# MicrobitBoardExtend.net
KiCad netlist of a schematic drawn in Altium Designer
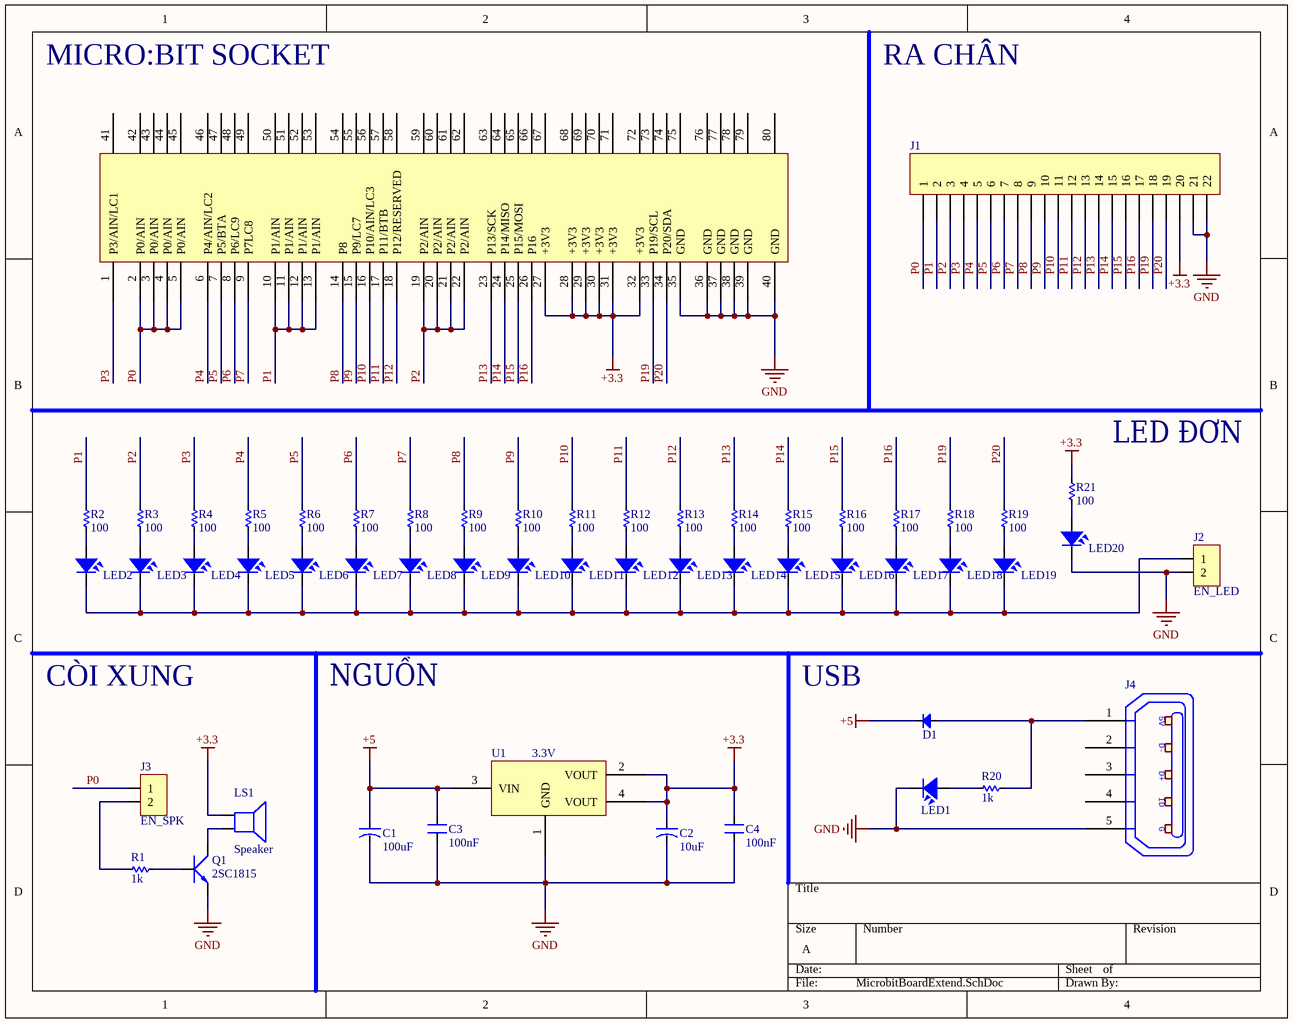
[diagram p0: MicrobitBoardExtend.SchDoc]

(export (version "E")
  (design (tool "Eeschema 10.0.6"))
  (components
    (comp (ref "BBC1")
      (value "BBC_SOCKET")
      (footprint "BBC_SK_DIP")
      (libsource (lib "microbit") (part "BBC_SOCKET"))
    )
    (comp (ref "C1")
      (value "100uF")
      (footprint "CA-ALU-6.3")
      (description "Capacitor (Semiconductor SIM Model)")
      (fields (field (name "PUBLISHER") "Altium Limited"))
      (libsource (lib "LIBRARY") (part "CN-ALU-DIP"))
    )
    (comp (ref "C2")
      (value "10uF")
      (footprint "CA-ALU-5")
      (description "Capacitor (Semiconductor SIM Model)")
      (fields (field (name "PUBLISHER") "Altium Limited"))
      (libsource (lib "LIBRARY") (part "CN-ALU-DIP"))
    )
    (comp (ref "C3") (value "100nF") (footprint "CN-SMD-0805") (libsource (lib "LIBRARY") (part "CN")))
    (comp (ref "C4") (value "100nF") (footprint "CN-SMD-0805") (libsource (lib "LIBRARY") (part "CN")))
    (comp (ref "D1")
      (value "SS34")
      (footprint "DIO-SMD-106")
      (description "Default Diode")
      (fields (field (name "PUBLISHER") "Altium Limited"))
      (libsource (lib "LIBRARY") (part "Diode SMD"))
    )
    (comp (ref "J1")
      (value "JP22")
      (footprint "JP22-D1T")
      (description "WR-PHD 2.54 mm Angled Socket Header")
      (fields
        (field (name "MANUFACTURER") "Würth Elektronik eiSos GmbH")
        (field (name "PARTNO") "613022143121")
        (field (name "CREATED BY") "Karrer Zheng")
      )
      (libsource (lib "LIBRARY") (part "JP22"))
    )
    (comp (ref "J2")
      (value "EN_LED")
      (footprint "JP2-CLOSED")
      (description "WR-PHD 2.54 mm Angled Socket Header")
      (fields
        (field (name "MANUFACTURER") "Würth Elektronik eiSos GmbH")
        (field (name "PARTNO") "613002143121")
        (field (name "CREATED BY") "Karrer Zheng")
      )
      (libsource (lib "LIBRARY") (part "JP2"))
    )
    (comp (ref "J3")
      (value "EN_SPK")
      (footprint "JP2-CLOSED")
      (description "WR-PHD 2.54 mm Angled Socket Header")
      (fields
        (field (name "MANUFACTURER") "Würth Elektronik eiSos GmbH")
        (field (name "PARTNO") "613002143121")
        (field (name "CREATED BY") "Karrer Zheng")
      )
      (libsource (lib "LIBRARY") (part "JP2"))
    )
    (comp (ref "J4")
      (value "PWR")
      (footprint "USB-M1")
      (fields
        (field (name "MANUFACTURER") "FCI")
        (field (name "MANUFACTURER PART NUMBER") "10118193-0001LF")
        (field (name ".CREATOR") "MM")
        (field (name ".CHECKED PCB") "RF")
        (field (name ".CHECKED SCH") "MM")
      )
      (libsource (lib "LIBRARY") (part "USB-5"))
    )
    (comp (ref "LED1")
      (value "PWR")
      (footprint "LED-0805-Green")
      (libsource (lib "LIBRARY") (part "LED SMD"))
    )
    (comp (ref "LED2")
      (value "LED")
      (footprint "LED-3MM-BLUE")
      (description "LED Single colour Green and Red")
      (libsource (lib "LIBRARY") (part "LED"))
    )
    (comp (ref "LED3")
      (value "LED")
      (footprint "LED-3MM-BLUE")
      (description "LED Single colour Green and Red")
      (libsource (lib "LIBRARY") (part "LED"))
    )
    (comp (ref "LED4")
      (value "LED")
      (footprint "LED-3MM-BLUE")
      (description "LED Single colour Green and Red")
      (libsource (lib "LIBRARY") (part "LED"))
    )
    (comp (ref "LED5")
      (value "LED")
      (footprint "LED-3MM-BLUE")
      (description "LED Single colour Green and Red")
      (libsource (lib "LIBRARY") (part "LED"))
    )
    (comp (ref "LED6")
      (value "LED")
      (footprint "LED-3MM-BLUE")
      (description "LED Single colour Green and Red")
      (libsource (lib "LIBRARY") (part "LED"))
    )
    (comp (ref "LED7")
      (value "LED")
      (footprint "LED-3MM-BLUE")
      (description "LED Single colour Green and Red")
      (libsource (lib "LIBRARY") (part "LED"))
    )
    (comp (ref "LED8")
      (value "LED")
      (footprint "LED-3MM-BLUE")
      (description "LED Single colour Green and Red")
      (libsource (lib "LIBRARY") (part "LED"))
    )
    (comp (ref "LED9")
      (value "LED")
      (footprint "LED-3MM-BLUE")
      (description "LED Single colour Green and Red")
      (libsource (lib "LIBRARY") (part "LED"))
    )
    (comp (ref "LED10")
      (value "LED")
      (footprint "LED-3MM-BLUE")
      (description "LED Single colour Green and Red")
      (libsource (lib "LIBRARY") (part "LED"))
    )
    (comp (ref "LED11")
      (value "LED")
      (footprint "LED-3MM-BLUE")
      (description "LED Single colour Green and Red")
      (libsource (lib "LIBRARY") (part "LED"))
    )
    (comp (ref "LED12")
      (value "LED")
      (footprint "LED-3MM-BLUE")
      (description "LED Single colour Green and Red")
      (libsource (lib "LIBRARY") (part "LED"))
    )
    (comp (ref "LED13")
      (value "LED")
      (footprint "LED-3MM-BLUE")
      (description "LED Single colour Green and Red")
      (libsource (lib "LIBRARY") (part "LED"))
    )
    (comp (ref "LED14")
      (value "LED")
      (footprint "LED-3MM-BLUE")
      (description "LED Single colour Green and Red")
      (libsource (lib "LIBRARY") (part "LED"))
    )
    (comp (ref "LED15")
      (value "LED")
      (footprint "LED-3MM-BLUE")
      (description "LED Single colour Green and Red")
      (libsource (lib "LIBRARY") (part "LED"))
    )
    (comp (ref "LED16")
      (value "LED")
      (footprint "LED-3MM-BLUE")
      (description "LED Single colour Green and Red")
      (libsource (lib "LIBRARY") (part "LED"))
    )
    (comp (ref "LED17")
      (value "LED")
      (footprint "LED-3MM-BLUE")
      (description "LED Single colour Green and Red")
      (libsource (lib "LIBRARY") (part "LED"))
    )
    (comp (ref "LED18")
      (value "LED")
      (footprint "LED-3MM-BLUE")
      (description "LED Single colour Green and Red")
      (libsource (lib "LIBRARY") (part "LED"))
    )
    (comp (ref "LED19")
      (value "LED")
      (footprint "LED-3MM-BLUE")
      (description "LED Single colour Green and Red")
      (libsource (lib "LIBRARY") (part "LED"))
    )
    (comp (ref "LED20")
      (value "3V3")
      (footprint "LED-0805-Green")
      (libsource (lib "LIBRARY") (part "LED SMD"))
    )
    (comp (ref "LS1")
      (value "Speaker")
      (footprint "SPEAKER")
      (description "Loudspeaker")
      (fields (field (name "PUBLISHER") "Altium Limited"))
      (libsource (lib "LIBRARY") (part "Speaker"))
    )
    (comp (ref "Q1")
      (value "2SC1815")
      (footprint "SOT23-321")
      (description "NPN 600mW, ECB")
      (libsource (lib "LIBRARY") (part "2SC1815"))
    )
    (comp (ref "R1")
      (value "1k")
      (footprint "RES-SMD-0805")
      (description "Resistor")
      (fields
        (field (name "MANUFACTURER") "Generic Components")
        (field (name "PUBLISHER") "Altium Hobart Technology Centre")
      )
      (libsource (lib "LIBRARY") (part "Res-SMD"))
    )
    (comp (ref "R2")
      (value "100")
      (footprint "RES-SMD-0805")
      (description "Resistor")
      (fields
        (field (name "MANUFACTURER") "Generic Components")
        (field (name "PUBLISHER") "Altium Hobart Technology Centre")
      )
      (libsource (lib "LIBRARY") (part "Res-SMD"))
    )
    (comp (ref "R3")
      (value "100")
      (footprint "RES-SMD-0805")
      (description "Resistor")
      (fields
        (field (name "MANUFACTURER") "Generic Components")
        (field (name "PUBLISHER") "Altium Hobart Technology Centre")
      )
      (libsource (lib "LIBRARY") (part "Res-SMD"))
    )
    (comp (ref "R4")
      (value "100")
      (footprint "RES-SMD-0805")
      (description "Resistor")
      (fields
        (field (name "MANUFACTURER") "Generic Components")
        (field (name "PUBLISHER") "Altium Hobart Technology Centre")
      )
      (libsource (lib "LIBRARY") (part "Res-SMD"))
    )
    (comp (ref "R5")
      (value "100")
      (footprint "RES-SMD-0805")
      (description "Resistor")
      (fields
        (field (name "MANUFACTURER") "Generic Components")
        (field (name "PUBLISHER") "Altium Hobart Technology Centre")
      )
      (libsource (lib "LIBRARY") (part "Res-SMD"))
    )
    (comp (ref "R6")
      (value "100")
      (footprint "RES-SMD-0805")
      (description "Resistor")
      (fields
        (field (name "MANUFACTURER") "Generic Components")
        (field (name "PUBLISHER") "Altium Hobart Technology Centre")
      )
      (libsource (lib "LIBRARY") (part "Res-SMD"))
    )
    (comp (ref "R7")
      (value "100")
      (footprint "RES-SMD-0805")
      (description "Resistor")
      (fields
        (field (name "MANUFACTURER") "Generic Components")
        (field (name "PUBLISHER") "Altium Hobart Technology Centre")
      )
      (libsource (lib "LIBRARY") (part "Res-SMD"))
    )
    (comp (ref "R8")
      (value "100")
      (footprint "RES-SMD-0805")
      (description "Resistor")
      (fields
        (field (name "MANUFACTURER") "Generic Components")
        (field (name "PUBLISHER") "Altium Hobart Technology Centre")
      )
      (libsource (lib "LIBRARY") (part "Res-SMD"))
    )
    (comp (ref "R9")
      (value "100")
      (footprint "RES-SMD-0805")
      (description "Resistor")
      (fields
        (field (name "MANUFACTURER") "Generic Components")
        (field (name "PUBLISHER") "Altium Hobart Technology Centre")
      )
      (libsource (lib "LIBRARY") (part "Res-SMD"))
    )
    (comp (ref "R10")
      (value "100")
      (footprint "RES-SMD-0805")
      (description "Resistor")
      (fields
        (field (name "MANUFACTURER") "Generic Components")
        (field (name "PUBLISHER") "Altium Hobart Technology Centre")
      )
      (libsource (lib "LIBRARY") (part "Res-SMD"))
    )
    (comp (ref "R11")
      (value "100")
      (footprint "RES-SMD-0805")
      (description "Resistor")
      (fields
        (field (name "MANUFACTURER") "Generic Components")
        (field (name "PUBLISHER") "Altium Hobart Technology Centre")
      )
      (libsource (lib "LIBRARY") (part "Res-SMD"))
    )
    (comp (ref "R12")
      (value "100")
      (footprint "RES-SMD-0805")
      (description "Resistor")
      (fields
        (field (name "MANUFACTURER") "Generic Components")
        (field (name "PUBLISHER") "Altium Hobart Technology Centre")
      )
      (libsource (lib "LIBRARY") (part "Res-SMD"))
    )
    (comp (ref "R13")
      (value "100")
      (footprint "RES-SMD-0805")
      (description "Resistor")
      (fields
        (field (name "MANUFACTURER") "Generic Components")
        (field (name "PUBLISHER") "Altium Hobart Technology Centre")
      )
      (libsource (lib "LIBRARY") (part "Res-SMD"))
    )
    (comp (ref "R14")
      (value "100")
      (footprint "RES-SMD-0805")
      (description "Resistor")
      (fields
        (field (name "MANUFACTURER") "Generic Components")
        (field (name "PUBLISHER") "Altium Hobart Technology Centre")
      )
      (libsource (lib "LIBRARY") (part "Res-SMD"))
    )
    (comp (ref "R15")
      (value "100")
      (footprint "RES-SMD-0805")
      (description "Resistor")
      (fields
        (field (name "MANUFACTURER") "Generic Components")
        (field (name "PUBLISHER") "Altium Hobart Technology Centre")
      )
      (libsource (lib "LIBRARY") (part "Res-SMD"))
    )
    (comp (ref "R16")
      (value "100")
      (footprint "RES-SMD-0805")
      (description "Resistor")
      (fields
        (field (name "MANUFACTURER") "Generic Components")
        (field (name "PUBLISHER") "Altium Hobart Technology Centre")
      )
      (libsource (lib "LIBRARY") (part "Res-SMD"))
    )
    (comp (ref "R17")
      (value "100")
      (footprint "RES-SMD-0805")
      (description "Resistor")
      (fields
        (field (name "MANUFACTURER") "Generic Components")
        (field (name "PUBLISHER") "Altium Hobart Technology Centre")
      )
      (libsource (lib "LIBRARY") (part "Res-SMD"))
    )
    (comp (ref "R18")
      (value "100")
      (footprint "RES-SMD-0805")
      (description "Resistor")
      (fields
        (field (name "MANUFACTURER") "Generic Components")
        (field (name "PUBLISHER") "Altium Hobart Technology Centre")
      )
      (libsource (lib "LIBRARY") (part "Res-SMD"))
    )
    (comp (ref "R19")
      (value "100")
      (footprint "RES-SMD-0805")
      (description "Resistor")
      (fields
        (field (name "MANUFACTURER") "Generic Components")
        (field (name "PUBLISHER") "Altium Hobart Technology Centre")
      )
      (libsource (lib "LIBRARY") (part "Res-SMD"))
    )
    (comp (ref "R20")
      (value "1k")
      (footprint "RES-SMD-0805")
      (description "Resistor")
      (fields
        (field (name "MANUFACTURER") "Generic Components")
        (field (name "PUBLISHER") "Altium Hobart Technology Centre")
      )
      (libsource (lib "LIBRARY") (part "Res-SMD"))
    )
    (comp (ref "R21")
      (value "100")
      (footprint "RES-SMD-0805")
      (description "Resistor")
      (fields
        (field (name "MANUFACTURER") "Generic Components")
        (field (name "PUBLISHER") "Altium Hobart Technology Centre")
      )
      (libsource (lib "LIBRARY") (part "Res-SMD"))
    )
    (comp (ref "U1")
      (value "3.3V")
      (footprint "SOT89-150P410X160-3N")
      (description "Dán")
      (libsource (lib "THU VIEN SCH_04042017_1") (part "CJA _ 3.3V"))
    )
  )
  (nets
    (net (code "1") (name "+3.3") (class "Default")
      (node (ref "BBC1") (pin "27") (pinfunction "+3V3_27") (pintype "passive"))
      (node (ref "BBC1") (pin "28") (pinfunction "+3V3_28") (pintype "passive"))
      (node (ref "BBC1") (pin "29") (pinfunction "+3V3_29") (pintype "passive"))
      (node (ref "BBC1") (pin "30") (pinfunction "+3V3_30") (pintype "passive"))
      (node (ref "BBC1") (pin "31") (pinfunction "+3V3_31") (pintype "passive"))
      (node (ref "BBC1") (pin "32") (pinfunction "+3V3_32") (pintype "passive"))
      (node (ref "C2") (pin "1") (pinfunction "1_1") (pintype "passive"))
      (node (ref "C4") (pin "1") (pinfunction "1_1") (pintype "passive"))
      (node (ref "J1") (pin "20") (pinfunction "20_20") (pintype "passive"))
      (node (ref "LS1") (pin "1") (pinfunction "1_1") (pintype "passive"))
      (node (ref "R21") (pin "2") (pinfunction "2_2") (pintype "passive"))
      (node (ref "U1") (pin "2") (pinfunction "VOUT_2") (pintype "passive"))
      (node (ref "U1") (pin "4") (pinfunction "VOUT_4") (pintype "passive"))
    )
    (net (code "2") (name "+5") (class "Default")
      (node (ref "C1") (pin "1") (pinfunction "1_1") (pintype "passive"))
      (node (ref "C3") (pin "1") (pinfunction "1_1") (pintype "passive"))
      (node (ref "D1") (pin "2") (pinfunction "K_2") (pintype "passive"))
      (node (ref "U1") (pin "3") (pinfunction "VIN_3") (pintype "passive"))
    )
    (net (code "3") (name "/P0") (class "Default")
      (node (ref "BBC1") (pin "2") (pinfunction "P0/AIN_2") (pintype "passive"))
      (node (ref "BBC1") (pin "3") (pinfunction "P0/AIN_3") (pintype "passive"))
      (node (ref "BBC1") (pin "4") (pinfunction "P0/AIN_4") (pintype "passive"))
      (node (ref "BBC1") (pin "5") (pinfunction "P0/AIN_5") (pintype "passive"))
      (node (ref "J1") (pin "1") (pinfunction "1_1") (pintype "passive"))
      (node (ref "J3") (pin "1") (pinfunction "1_1") (pintype "passive"))
    )
    (net (code "4") (name "/P1") (class "Default")
      (node (ref "BBC1") (pin "10") (pinfunction "P1/AIN_10") (pintype "passive"))
      (node (ref "BBC1") (pin "11") (pinfunction "P1/AIN_11") (pintype "passive"))
      (node (ref "BBC1") (pin "12") (pinfunction "P1/AIN_12") (pintype "passive"))
      (node (ref "BBC1") (pin "13") (pinfunction "P1/AIN_13") (pintype "passive"))
      (node (ref "J1") (pin "2") (pinfunction "2_2") (pintype "passive"))
      (node (ref "R2") (pin "2") (pinfunction "2_2") (pintype "passive"))
    )
    (net (code "5") (name "/P2") (class "Default")
      (node (ref "BBC1") (pin "19") (pinfunction "P2/AIN_19") (pintype "passive"))
      (node (ref "BBC1") (pin "20") (pinfunction "P2/AIN_20") (pintype "passive"))
      (node (ref "BBC1") (pin "21") (pinfunction "P2/AIN_21") (pintype "passive"))
      (node (ref "BBC1") (pin "22") (pinfunction "P2/AIN_22") (pintype "passive"))
      (node (ref "J1") (pin "3") (pinfunction "3_3") (pintype "passive"))
      (node (ref "R3") (pin "2") (pinfunction "2_2") (pintype "passive"))
    )
    (net (code "6") (name "/P3") (class "Default")
      (node (ref "BBC1") (pin "1") (pinfunction "P3/AIN/LC1_1") (pintype "passive"))
      (node (ref "J1") (pin "4") (pinfunction "4_4") (pintype "passive"))
      (node (ref "R4") (pin "2") (pinfunction "2_2") (pintype "passive"))
    )
    (net (code "7") (name "/P4") (class "Default")
      (node (ref "BBC1") (pin "6") (pinfunction "P4/AIN/LC2_6") (pintype "passive"))
      (node (ref "J1") (pin "5") (pinfunction "5_5") (pintype "passive"))
      (node (ref "R5") (pin "2") (pinfunction "2_2") (pintype "passive"))
    )
    (net (code "8") (name "/P5") (class "Default")
      (node (ref "BBC1") (pin "7") (pinfunction "P5/BTA_7") (pintype "passive"))
      (node (ref "J1") (pin "6") (pinfunction "6_6") (pintype "passive"))
      (node (ref "R6") (pin "2") (pinfunction "2_2") (pintype "passive"))
    )
    (net (code "9") (name "/P6") (class "Default")
      (node (ref "BBC1") (pin "8") (pinfunction "P6/LC9_8") (pintype "passive"))
      (node (ref "J1") (pin "7") (pinfunction "7_7") (pintype "passive"))
      (node (ref "R7") (pin "2") (pinfunction "2_2") (pintype "passive"))
    )
    (net (code "10") (name "/P7") (class "Default")
      (node (ref "BBC1") (pin "9") (pinfunction "P7LC8_9") (pintype "passive"))
      (node (ref "J1") (pin "8") (pinfunction "8_8") (pintype "passive"))
      (node (ref "R8") (pin "2") (pinfunction "2_2") (pintype "passive"))
    )
    (net (code "11") (name "/P8") (class "Default")
      (node (ref "BBC1") (pin "14") (pinfunction "P8_14") (pintype "passive"))
      (node (ref "J1") (pin "9") (pinfunction "9_9") (pintype "passive"))
      (node (ref "R9") (pin "2") (pinfunction "2_2") (pintype "passive"))
    )
    (net (code "12") (name "/P9") (class "Default")
      (node (ref "BBC1") (pin "15") (pinfunction "P9/LC7_15") (pintype "passive"))
      (node (ref "J1") (pin "10") (pinfunction "10_10") (pintype "passive"))
      (node (ref "R10") (pin "2") (pinfunction "2_2") (pintype "passive"))
    )
    (net (code "13") (name "/P10") (class "Default")
      (node (ref "BBC1") (pin "16") (pinfunction "P10/AIN/LC3_16") (pintype "passive"))
      (node (ref "J1") (pin "11") (pinfunction "11_11") (pintype "passive"))
      (node (ref "R11") (pin "2") (pinfunction "2_2") (pintype "passive"))
    )
    (net (code "14") (name "/P11") (class "Default")
      (node (ref "BBC1") (pin "17") (pinfunction "P11/BTB_17") (pintype "passive"))
      (node (ref "J1") (pin "12") (pinfunction "12_12") (pintype "passive"))
      (node (ref "R12") (pin "2") (pinfunction "2_2") (pintype "passive"))
    )
    (net (code "15") (name "/P12") (class "Default")
      (node (ref "BBC1") (pin "18") (pinfunction "P12/RESERVED_18") (pintype "passive"))
      (node (ref "J1") (pin "13") (pinfunction "13_13") (pintype "passive"))
      (node (ref "R13") (pin "2") (pinfunction "2_2") (pintype "passive"))
    )
    (net (code "16") (name "/P13") (class "Default")
      (node (ref "BBC1") (pin "23") (pinfunction "P13/SCK_23") (pintype "passive"))
      (node (ref "J1") (pin "14") (pinfunction "14_14") (pintype "passive"))
      (node (ref "R14") (pin "2") (pinfunction "2_2") (pintype "passive"))
    )
    (net (code "17") (name "/P14") (class "Default")
      (node (ref "BBC1") (pin "24") (pinfunction "P14/MISO_24") (pintype "passive"))
      (node (ref "J1") (pin "15") (pinfunction "15_15") (pintype "passive"))
      (node (ref "R15") (pin "2") (pinfunction "2_2") (pintype "passive"))
    )
    (net (code "18") (name "/P15") (class "Default")
      (node (ref "BBC1") (pin "25") (pinfunction "P15/MOSI_25") (pintype "passive"))
      (node (ref "J1") (pin "16") (pinfunction "16_16") (pintype "passive"))
      (node (ref "R16") (pin "2") (pinfunction "2_2") (pintype "passive"))
    )
    (net (code "19") (name "/P16") (class "Default")
      (node (ref "BBC1") (pin "26") (pinfunction "P16_26") (pintype "passive"))
      (node (ref "J1") (pin "17") (pinfunction "17_17") (pintype "passive"))
      (node (ref "R17") (pin "2") (pinfunction "2_2") (pintype "passive"))
    )
    (net (code "20") (name "/P19") (class "Default")
      (node (ref "BBC1") (pin "33") (pinfunction "P19/SCL_33") (pintype "passive"))
      (node (ref "J1") (pin "18") (pinfunction "18_18") (pintype "passive"))
      (node (ref "R18") (pin "2") (pinfunction "2_2") (pintype "passive"))
    )
    (net (code "21") (name "/P20") (class "Default")
      (node (ref "BBC1") (pin "34") (pinfunction "P20/SDA_34") (pintype "passive"))
      (node (ref "J1") (pin "19") (pinfunction "19_19") (pintype "passive"))
      (node (ref "R19") (pin "2") (pinfunction "2_2") (pintype "passive"))
    )
    (net (code "22") (name "GND") (class "Default")
      (node (ref "BBC1") (pin "35") (pinfunction "GND_35") (pintype "passive"))
      (node (ref "BBC1") (pin "36") (pinfunction "GND_36") (pintype "passive"))
      (node (ref "BBC1") (pin "37") (pinfunction "GND_37") (pintype "passive"))
      (node (ref "BBC1") (pin "38") (pinfunction "GND_38") (pintype "passive"))
      (node (ref "BBC1") (pin "39") (pinfunction "GND_39") (pintype "passive"))
      (node (ref "BBC1") (pin "40") (pinfunction "GND_40") (pintype "passive"))
      (node (ref "C1") (pin "2") (pinfunction "2_2") (pintype "passive"))
      (node (ref "C2") (pin "2") (pinfunction "2_2") (pintype "passive"))
      (node (ref "C3") (pin "2") (pinfunction "2_2") (pintype "passive"))
      (node (ref "C4") (pin "2") (pinfunction "2_2") (pintype "passive"))
      (node (ref "J1") (pin "21") (pinfunction "21_21") (pintype "passive"))
      (node (ref "J1") (pin "22") (pinfunction "22_22") (pintype "passive"))
      (node (ref "J2") (pin "2") (pinfunction "2_2") (pintype "passive"))
      (node (ref "J4") (pin "5") (pinfunction "P5_5") (pintype "passive"))
      (node (ref "LED1") (pin "2") (pinfunction "2_2") (pintype "passive"))
      (node (ref "LED20") (pin "2") (pinfunction "2_2") (pintype "passive"))
      (node (ref "Q1") (pin "1") (pinfunction "E_1") (pintype "passive"))
      (node (ref "U1") (pin "1") (pinfunction "GND_1") (pintype "passive"))
    )
    (net (code "23") (name "Net-(D1-A)") (class "Default")
      (node (ref "D1") (pin "1") (pinfunction "A_1") (pintype "passive"))
      (node (ref "J4") (pin "1") (pinfunction "P1_1") (pintype "passive"))
      (node (ref "R20") (pin "1") (pinfunction "1_1") (pintype "passive"))
    )
    (net (code "24") (name "Net-(J2-Pad1)") (class "Default")
      (node (ref "J2") (pin "1") (pinfunction "1_1") (pintype "passive"))
      (node (ref "LED10") (pin "2") (pinfunction "2_2") (pintype "passive"))
      (node (ref "LED11") (pin "2") (pinfunction "2_2") (pintype "passive"))
      (node (ref "LED12") (pin "2") (pinfunction "2_2") (pintype "passive"))
      (node (ref "LED13") (pin "2") (pinfunction "2_2") (pintype "passive"))
      (node (ref "LED14") (pin "2") (pinfunction "2_2") (pintype "passive"))
      (node (ref "LED15") (pin "2") (pinfunction "2_2") (pintype "passive"))
      (node (ref "LED16") (pin "2") (pinfunction "2_2") (pintype "passive"))
      (node (ref "LED17") (pin "2") (pinfunction "2_2") (pintype "passive"))
      (node (ref "LED18") (pin "2") (pinfunction "2_2") (pintype "passive"))
      (node (ref "LED19") (pin "2") (pinfunction "2_2") (pintype "passive"))
      (node (ref "LED2") (pin "2") (pinfunction "2_2") (pintype "passive"))
      (node (ref "LED3") (pin "2") (pinfunction "2_2") (pintype "passive"))
      (node (ref "LED4") (pin "2") (pinfunction "2_2") (pintype "passive"))
      (node (ref "LED5") (pin "2") (pinfunction "2_2") (pintype "passive"))
      (node (ref "LED6") (pin "2") (pinfunction "2_2") (pintype "passive"))
      (node (ref "LED7") (pin "2") (pinfunction "2_2") (pintype "passive"))
      (node (ref "LED8") (pin "2") (pinfunction "2_2") (pintype "passive"))
      (node (ref "LED9") (pin "2") (pinfunction "2_2") (pintype "passive"))
    )
    (net (code "25") (name "Net-(J3-Pad2)") (class "Default")
      (node (ref "J3") (pin "2") (pinfunction "2_2") (pintype "passive"))
      (node (ref "R1") (pin "2") (pinfunction "2_2") (pintype "passive"))
    )
    (net (code "26") (name "Net-(LED1-Pad1)") (class "Default")
      (node (ref "LED1") (pin "1") (pinfunction "1_1") (pintype "passive"))
      (node (ref "R20") (pin "2") (pinfunction "2_2") (pintype "passive"))
    )
    (net (code "27") (name "Net-(LED2-Pad1)") (class "Default")
      (node (ref "LED2") (pin "1") (pinfunction "1_1") (pintype "passive"))
      (node (ref "R2") (pin "1") (pinfunction "1_1") (pintype "passive"))
    )
    (net (code "28") (name "Net-(LED3-Pad1)") (class "Default")
      (node (ref "LED3") (pin "1") (pinfunction "1_1") (pintype "passive"))
      (node (ref "R3") (pin "1") (pinfunction "1_1") (pintype "passive"))
    )
    (net (code "29") (name "Net-(LED4-Pad1)") (class "Default")
      (node (ref "LED4") (pin "1") (pinfunction "1_1") (pintype "passive"))
      (node (ref "R4") (pin "1") (pinfunction "1_1") (pintype "passive"))
    )
    (net (code "30") (name "Net-(LED5-Pad1)") (class "Default")
      (node (ref "LED5") (pin "1") (pinfunction "1_1") (pintype "passive"))
      (node (ref "R5") (pin "1") (pinfunction "1_1") (pintype "passive"))
    )
    (net (code "31") (name "Net-(LED6-Pad1)") (class "Default")
      (node (ref "LED6") (pin "1") (pinfunction "1_1") (pintype "passive"))
      (node (ref "R6") (pin "1") (pinfunction "1_1") (pintype "passive"))
    )
    (net (code "32") (name "Net-(LED7-Pad1)") (class "Default")
      (node (ref "LED7") (pin "1") (pinfunction "1_1") (pintype "passive"))
      (node (ref "R7") (pin "1") (pinfunction "1_1") (pintype "passive"))
    )
    (net (code "33") (name "Net-(LED8-Pad1)") (class "Default")
      (node (ref "LED8") (pin "1") (pinfunction "1_1") (pintype "passive"))
      (node (ref "R8") (pin "1") (pinfunction "1_1") (pintype "passive"))
    )
    (net (code "34") (name "Net-(LED9-Pad1)") (class "Default")
      (node (ref "LED9") (pin "1") (pinfunction "1_1") (pintype "passive"))
      (node (ref "R9") (pin "1") (pinfunction "1_1") (pintype "passive"))
    )
    (net (code "35") (name "Net-(LED10-Pad1)") (class "Default")
      (node (ref "LED10") (pin "1") (pinfunction "1_1") (pintype "passive"))
      (node (ref "R10") (pin "1") (pinfunction "1_1") (pintype "passive"))
    )
    (net (code "36") (name "Net-(LED11-Pad1)") (class "Default")
      (node (ref "LED11") (pin "1") (pinfunction "1_1") (pintype "passive"))
      (node (ref "R11") (pin "1") (pinfunction "1_1") (pintype "passive"))
    )
    (net (code "37") (name "Net-(LED12-Pad1)") (class "Default")
      (node (ref "LED12") (pin "1") (pinfunction "1_1") (pintype "passive"))
      (node (ref "R12") (pin "1") (pinfunction "1_1") (pintype "passive"))
    )
    (net (code "38") (name "Net-(LED13-Pad1)") (class "Default")
      (node (ref "LED13") (pin "1") (pinfunction "1_1") (pintype "passive"))
      (node (ref "R13") (pin "1") (pinfunction "1_1") (pintype "passive"))
    )
    (net (code "39") (name "Net-(LED14-Pad1)") (class "Default")
      (node (ref "LED14") (pin "1") (pinfunction "1_1") (pintype "passive"))
      (node (ref "R14") (pin "1") (pinfunction "1_1") (pintype "passive"))
    )
    (net (code "40") (name "Net-(LED15-Pad1)") (class "Default")
      (node (ref "LED15") (pin "1") (pinfunction "1_1") (pintype "passive"))
      (node (ref "R15") (pin "1") (pinfunction "1_1") (pintype "passive"))
    )
    (net (code "41") (name "Net-(LED16-Pad1)") (class "Default")
      (node (ref "LED16") (pin "1") (pinfunction "1_1") (pintype "passive"))
      (node (ref "R16") (pin "1") (pinfunction "1_1") (pintype "passive"))
    )
    (net (code "42") (name "Net-(LED17-Pad1)") (class "Default")
      (node (ref "LED17") (pin "1") (pinfunction "1_1") (pintype "passive"))
      (node (ref "R17") (pin "1") (pinfunction "1_1") (pintype "passive"))
    )
    (net (code "43") (name "Net-(LED18-Pad1)") (class "Default")
      (node (ref "LED18") (pin "1") (pinfunction "1_1") (pintype "passive"))
      (node (ref "R18") (pin "1") (pinfunction "1_1") (pintype "passive"))
    )
    (net (code "44") (name "Net-(LED19-Pad1)") (class "Default")
      (node (ref "LED19") (pin "1") (pinfunction "1_1") (pintype "passive"))
      (node (ref "R19") (pin "1") (pinfunction "1_1") (pintype "passive"))
    )
    (net (code "45") (name "Net-(LED20-Pad1)") (class "Default")
      (node (ref "LED20") (pin "1") (pinfunction "1_1") (pintype "passive"))
      (node (ref "R21") (pin "1") (pinfunction "1_1") (pintype "passive"))
    )
    (net (code "46") (name "Net-(Q1-B)") (class "Default")
      (node (ref "Q1") (pin "3") (pinfunction "B_3") (pintype "passive"))
      (node (ref "R1") (pin "1") (pinfunction "1_1") (pintype "passive"))
    )
    (net (code "47") (name "Net-(Q1-C)") (class "Default")
      (node (ref "LS1") (pin "2") (pinfunction "2_2") (pintype "passive"))
      (node (ref "Q1") (pin "2") (pinfunction "C_2") (pintype "passive"))
    )
    (net (code "48") (name "unconnected-(BBC1-+3V3-Pad67)") (class "Default")
      (node (ref "BBC1") (pin "67") (pinfunction "+3V3_67") (pintype "passive"))
    )
    (net (code "49") (name "unconnected-(BBC1-+3V3-Pad68)") (class "Default")
      (node (ref "BBC1") (pin "68") (pinfunction "+3V3_68") (pintype "passive"))
    )
    (net (code "50") (name "unconnected-(BBC1-+3V3-Pad69)") (class "Default")
      (node (ref "BBC1") (pin "69") (pinfunction "+3V3_69") (pintype "passive"))
    )
    (net (code "51") (name "unconnected-(BBC1-+3V3-Pad70)") (class "Default")
      (node (ref "BBC1") (pin "70") (pinfunction "+3V3_70") (pintype "passive"))
    )
    (net (code "52") (name "unconnected-(BBC1-+3V3-Pad71)") (class "Default")
      (node (ref "BBC1") (pin "71") (pinfunction "+3V3_71") (pintype "passive"))
    )
    (net (code "53") (name "unconnected-(BBC1-+3V3-Pad72)") (class "Default")
      (node (ref "BBC1") (pin "72") (pinfunction "+3V3_72") (pintype "passive"))
    )
    (net (code "54") (name "unconnected-(BBC1-GND-Pad75)") (class "Default")
      (node (ref "BBC1") (pin "75") (pinfunction "GND_75") (pintype "passive"))
    )
    (net (code "55") (name "unconnected-(BBC1-GND-Pad76)") (class "Default")
      (node (ref "BBC1") (pin "76") (pinfunction "GND_76") (pintype "passive"))
    )
    (net (code "56") (name "unconnected-(BBC1-GND-Pad77)") (class "Default")
      (node (ref "BBC1") (pin "77") (pinfunction "GND_77") (pintype "passive"))
    )
    (net (code "57") (name "unconnected-(BBC1-GND-Pad78)") (class "Default")
      (node (ref "BBC1") (pin "78") (pinfunction "GND_78") (pintype "passive"))
    )
    (net (code "58") (name "unconnected-(BBC1-GND-Pad79)") (class "Default")
      (node (ref "BBC1") (pin "79") (pinfunction "GND_79") (pintype "passive"))
    )
    (net (code "59") (name "unconnected-(BBC1-GND-Pad80)") (class "Default")
      (node (ref "BBC1") (pin "80") (pinfunction "GND_80") (pintype "passive"))
    )
    (net (code "60") (name "unconnected-(BBC1-P0-Pad42)") (class "Default")
      (node (ref "BBC1") (pin "42") (pinfunction "P0_42") (pintype "passive"))
    )
    (net (code "61") (name "unconnected-(BBC1-P0-Pad43)") (class "Default")
      (node (ref "BBC1") (pin "43") (pinfunction "P0_43") (pintype "passive"))
    )
    (net (code "62") (name "unconnected-(BBC1-P0-Pad44)") (class "Default")
      (node (ref "BBC1") (pin "44") (pinfunction "P0_44") (pintype "passive"))
    )
    (net (code "63") (name "unconnected-(BBC1-P0-Pad45)") (class "Default")
      (node (ref "BBC1") (pin "45") (pinfunction "P0_45") (pintype "passive"))
    )
    (net (code "64") (name "unconnected-(BBC1-P1-Pad50)") (class "Default")
      (node (ref "BBC1") (pin "50") (pinfunction "P1_50") (pintype "passive"))
    )
    (net (code "65") (name "unconnected-(BBC1-P1-Pad51)") (class "Default")
      (node (ref "BBC1") (pin "51") (pinfunction "P1_51") (pintype "passive"))
    )
    (net (code "66") (name "unconnected-(BBC1-P1-Pad52)") (class "Default")
      (node (ref "BBC1") (pin "52") (pinfunction "P1_52") (pintype "passive"))
    )
    (net (code "67") (name "unconnected-(BBC1-P1-Pad53)") (class "Default")
      (node (ref "BBC1") (pin "53") (pinfunction "P1_53") (pintype "passive"))
    )
    (net (code "68") (name "unconnected-(BBC1-P2-Pad59)") (class "Default")
      (node (ref "BBC1") (pin "59") (pinfunction "P2_59") (pintype "passive"))
    )
    (net (code "69") (name "unconnected-(BBC1-P2-Pad60)") (class "Default")
      (node (ref "BBC1") (pin "60") (pinfunction "P2_60") (pintype "passive"))
    )
    (net (code "70") (name "unconnected-(BBC1-P2-Pad61)") (class "Default")
      (node (ref "BBC1") (pin "61") (pinfunction "P2_61") (pintype "passive"))
    )
    (net (code "71") (name "unconnected-(BBC1-P2-Pad62)") (class "Default")
      (node (ref "BBC1") (pin "62") (pinfunction "P2_62") (pintype "passive"))
    )
    (net (code "72") (name "unconnected-(BBC1-P3-Pad41)") (class "Default")
      (node (ref "BBC1") (pin "41") (pinfunction "P3_41") (pintype "passive"))
    )
    (net (code "73") (name "unconnected-(BBC1-P4-Pad46)") (class "Default")
      (node (ref "BBC1") (pin "46") (pinfunction "P4_46") (pintype "passive"))
    )
    (net (code "74") (name "unconnected-(BBC1-P5-Pad47)") (class "Default")
      (node (ref "BBC1") (pin "47") (pinfunction "P5_47") (pintype "passive"))
    )
    (net (code "75") (name "unconnected-(BBC1-P6-Pad48)") (class "Default")
      (node (ref "BBC1") (pin "48") (pinfunction "P6_48") (pintype "passive"))
    )
    (net (code "76") (name "unconnected-(BBC1-P7-Pad49)") (class "Default")
      (node (ref "BBC1") (pin "49") (pinfunction "P7_49") (pintype "passive"))
    )
    (net (code "77") (name "unconnected-(BBC1-P8-Pad54)") (class "Default")
      (node (ref "BBC1") (pin "54") (pinfunction "P8_54") (pintype "passive"))
    )
    (net (code "78") (name "unconnected-(BBC1-P9-Pad55)") (class "Default")
      (node (ref "BBC1") (pin "55") (pinfunction "P9_55") (pintype "passive"))
    )
    (net (code "79") (name "unconnected-(BBC1-P10-Pad56)") (class "Default")
      (node (ref "BBC1") (pin "56") (pinfunction "P10_56") (pintype "passive"))
    )
    (net (code "80") (name "unconnected-(BBC1-P11-Pad57)") (class "Default")
      (node (ref "BBC1") (pin "57") (pinfunction "P11_57") (pintype "passive"))
    )
    (net (code "81") (name "unconnected-(BBC1-P12-Pad58)") (class "Default")
      (node (ref "BBC1") (pin "58") (pinfunction "P12_58") (pintype "passive"))
    )
    (net (code "82") (name "unconnected-(BBC1-P13-Pad63)") (class "Default")
      (node (ref "BBC1") (pin "63") (pinfunction "P13_63") (pintype "passive"))
    )
    (net (code "83") (name "unconnected-(BBC1-P14-Pad64)") (class "Default")
      (node (ref "BBC1") (pin "64") (pinfunction "P14_64") (pintype "passive"))
    )
    (net (code "84") (name "unconnected-(BBC1-P15-Pad65)") (class "Default")
      (node (ref "BBC1") (pin "65") (pinfunction "P15_65") (pintype "passive"))
    )
    (net (code "85") (name "unconnected-(BBC1-P16-Pad66)") (class "Default")
      (node (ref "BBC1") (pin "66") (pinfunction "P16_66") (pintype "passive"))
    )
    (net (code "86") (name "unconnected-(BBC1-P19-Pad73)") (class "Default")
      (node (ref "BBC1") (pin "73") (pinfunction "P19_73") (pintype "passive"))
    )
    (net (code "87") (name "unconnected-(BBC1-P20-Pad74)") (class "Default")
      (node (ref "BBC1") (pin "74") (pinfunction "P20_74") (pintype "passive"))
    )
    (net (code "88") (name "unconnected-(J4-P2-Pad2)") (class "Default")
      (node (ref "J4") (pin "2") (pinfunction "P2_2") (pintype "passive"))
    )
    (net (code "89") (name "unconnected-(J4-P3-Pad3)") (class "Default")
      (node (ref "J4") (pin "3") (pinfunction "P3_3") (pintype "passive"))
    )
    (net (code "90") (name "unconnected-(J4-P4-Pad4)") (class "Default")
      (node (ref "J4") (pin "4") (pinfunction "P4_4") (pintype "passive"))
    )
  )
)
